# Interfaces.net
KiCad netlist of a schematic drawn in Altium Designer
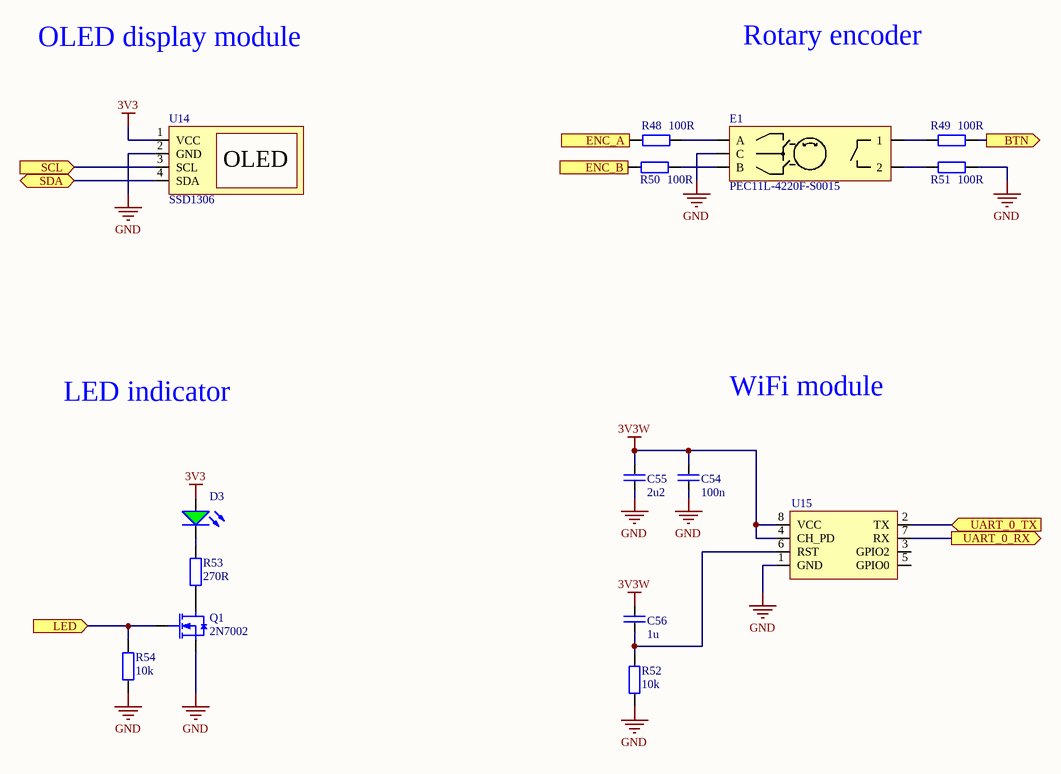
[diagram p0: Interfaces.SchDoc]

(export (version "E")
  (design (tool "Eeschema 10.0.6"))
  (components
    (comp (ref "C54")
      (value "100n")
      (footprint "C_0603")
      (description "Generic capacitor")
      (libsource (lib "DAQ_REV_B") (part "Capacitor"))
    )
    (comp (ref "C55")
      (value "2u2")
      (footprint "C_0603")
      (description "Generic capacitor")
      (libsource (lib "DAQ_REV_B") (part "Capacitor"))
    )
    (comp (ref "C56")
      (value "1u")
      (footprint "C_0603")
      (description "Generic capacitor")
      (libsource (lib "DAQ_REV_B") (part "Capacitor"))
    )
    (comp (ref "D3")
      (value "LED Green")
      (footprint "LED_0603")
      (description "Generic LED Green")
      (libsource (lib "DAQ_REV_B") (part "LED Green"))
    )
    (comp (ref "E1")
      (value "PEC11L-4220F-S0015")
      (footprint "PEC11L-4220F-S0015")
      (description "Low Profile Encoder 15 PPR 2 Bit Quadrature 5VDC at 10 mA IP40 PCB Mount")
      (fields (field (name "PART NUMBER") "XRE0000") (field (name "MANUFACTURER") "BOURNS"))
      (libsource (lib "DAQ_REV_B") (part "PEC11L-4220F-S0015"))
    )
    (comp (ref "Q1")
      (value "2N7002")
      (footprint "SOT23-3")
      (description "60V 0.3A N-channel MOSFET")
      (fields (field (name "PART NUMBER") "XMN0002") (field (name "MANUFACTURER") "NXP"))
      (libsource (lib "DAQ_REV_B") (part "2N7002"))
    )
    (comp (ref "R48")
      (value "100R")
      (footprint "R_0603")
      (description "Generic resistor")
      (libsource (lib "DAQ_REV_B") (part "Resistor"))
    )
    (comp (ref "R49")
      (value "100R")
      (footprint "R_0603")
      (description "Generic resistor")
      (libsource (lib "DAQ_REV_B") (part "Resistor"))
    )
    (comp (ref "R50")
      (value "100R")
      (footprint "R_0603")
      (description "Generic resistor")
      (libsource (lib "DAQ_REV_B") (part "Resistor"))
    )
    (comp (ref "R51")
      (value "100R")
      (footprint "R_0603")
      (description "Generic resistor")
      (libsource (lib "DAQ_REV_B") (part "Resistor"))
    )
    (comp (ref "R52")
      (value "10k")
      (footprint "R_0603")
      (description "Generic resistor")
      (libsource (lib "DAQ_REV_B") (part "Resistor"))
    )
    (comp (ref "R53")
      (value "270R")
      (footprint "R_0603")
      (description "Generic resistor")
      (libsource (lib "DAQ_REV_B") (part "Resistor"))
    )
    (comp (ref "R54")
      (value "10k")
      (footprint "R_0603")
      (description "Generic resistor")
      (libsource (lib "DAQ_REV_B") (part "Resistor"))
    )
    (comp (ref "U14")
      (value "SSD1306")
      (footprint "OLED1")
      (description "Oled display module")
      (fields (field (name "PART NUMBER") "OLM0000"))
      (libsource (lib "DAQ_REV_B") (part "OLED_SSD1306"))
    )
    (comp (ref "U15")
      (value "ESP-01")
      (footprint "ESP-01")
      (description "WIFI module")
      (fields (field (name "PART NUMBER") "XWM0000"))
      (libsource (lib "DAQ_REV_B") (part "ESP-01"))
    )
  )
  (nets
    (net (code "1") (name "/BTN") (class "Default") (node (ref "R49") (pin "2") (pintype "passive")))
    (net (code "2") (name "/ENC_A") (class "Default") (node (ref "R48") (pin "1") (pintype "passive")))
    (net (code "3") (name "/ENC_B") (class "Default") (node (ref "R50") (pin "1") (pintype "passive")))
    (net (code "4") (name "/LED") (class "Default")
      (node (ref "Q1") (pin "1") (pinfunction "G_1") (pintype "passive"))
      (node (ref "R54") (pin "2") (pintype "passive"))
    )
    (net (code "5") (name "/SCL") (class "Default")
      (node (ref "U14") (pin "3") (pinfunction "SCL_3") (pintype "passive"))
    )
    (net (code "6") (name "/SDA") (class "Default")
      (node (ref "U14") (pin "4") (pinfunction "SDA_4") (pintype "passive"))
    )
    (net (code "7") (name "/UART_0_RX") (class "Default")
      (node (ref "U15") (pin "7") (pinfunction "RX_7") (pintype "passive"))
    )
    (net (code "8") (name "/UART_0_TX") (class "Default")
      (node (ref "U15") (pin "2") (pinfunction "TX_2") (pintype "passive"))
    )
    (net (code "9") (name "3V3") (class "Default")
      (node (ref "D3") (pin "2") (pinfunction "+_2") (pintype "passive"))
      (node (ref "U14") (pin "1") (pinfunction "VCC_1") (pintype "passive"))
    )
    (net (code "10") (name "3V3W") (class "Default")
      (node (ref "C54") (pin "2") (pinfunction "2_2") (pintype "passive"))
      (node (ref "C55") (pin "2") (pinfunction "2_2") (pintype "passive"))
      (node (ref "C56") (pin "2") (pinfunction "2_2") (pintype "passive"))
      (node (ref "U15") (pin "4") (pinfunction "CH_PD_4") (pintype "passive"))
      (node (ref "U15") (pin "8") (pinfunction "VCC_8") (pintype "passive"))
    )
    (net (code "11") (name "GND") (class "Default")
      (node (ref "C54") (pin "1") (pinfunction "1_1") (pintype "passive"))
      (node (ref "C55") (pin "1") (pinfunction "1_1") (pintype "passive"))
      (node (ref "E1") (pin "C") (pinfunction "C_C") (pintype "passive"))
      (node (ref "Q1") (pin "2") (pinfunction "S_2") (pintype "passive"))
      (node (ref "R51") (pin "2") (pintype "passive"))
      (node (ref "R52") (pin "1") (pintype "passive"))
      (node (ref "R54") (pin "1") (pintype "passive"))
      (node (ref "U14") (pin "2") (pinfunction "GND_2") (pintype "passive"))
      (node (ref "U15") (pin "1") (pinfunction "GND_1") (pintype "passive"))
    )
    (net (code "12") (name "Net-(D3--)") (class "Default")
      (node (ref "D3") (pin "1") (pinfunction "-_1") (pintype "passive"))
      (node (ref "R53") (pin "2") (pintype "passive"))
    )
    (net (code "13") (name "Net-(E1-Pad1)") (class "Default")
      (node (ref "E1") (pin "1") (pinfunction "1_1") (pintype "passive"))
      (node (ref "R49") (pin "1") (pintype "passive"))
    )
    (net (code "14") (name "Net-(E1-Pad2)") (class "Default")
      (node (ref "E1") (pin "2") (pinfunction "2_2") (pintype "passive"))
      (node (ref "R51") (pin "1") (pintype "passive"))
    )
    (net (code "15") (name "Net-(E1-PadA)") (class "Default")
      (node (ref "E1") (pin "A") (pinfunction "A_A") (pintype "passive"))
      (node (ref "R48") (pin "2") (pintype "passive"))
    )
    (net (code "16") (name "Net-(E1-PadB)") (class "Default")
      (node (ref "E1") (pin "B") (pinfunction "B_B") (pintype "passive"))
      (node (ref "R50") (pin "2") (pintype "passive"))
    )
    (net (code "17") (name "Net-(Q1-D)") (class "Default")
      (node (ref "Q1") (pin "3") (pinfunction "D_3") (pintype "passive"))
      (node (ref "R53") (pin "1") (pintype "passive"))
    )
    (net (code "18") (name "Net-(U15-RST)") (class "Default")
      (node (ref "C56") (pin "1") (pinfunction "1_1") (pintype "passive"))
      (node (ref "R52") (pin "2") (pintype "passive"))
      (node (ref "U15") (pin "6") (pinfunction "RST_6") (pintype "passive"))
    )
    (net (code "19") (name "unconnected-(U15-GPIO0-Pad5)") (class "Default")
      (node (ref "U15") (pin "5") (pinfunction "GPIO0_5") (pintype "passive"))
    )
    (net (code "20") (name "unconnected-(U15-GPIO2-Pad3)") (class "Default")
      (node (ref "U15") (pin "3") (pinfunction "GPIO2_3") (pintype "passive"))
    )
  )
)
